# SOIC8-TSSOP8.net
KiCad netlist of a schematic drawn in EAGLE
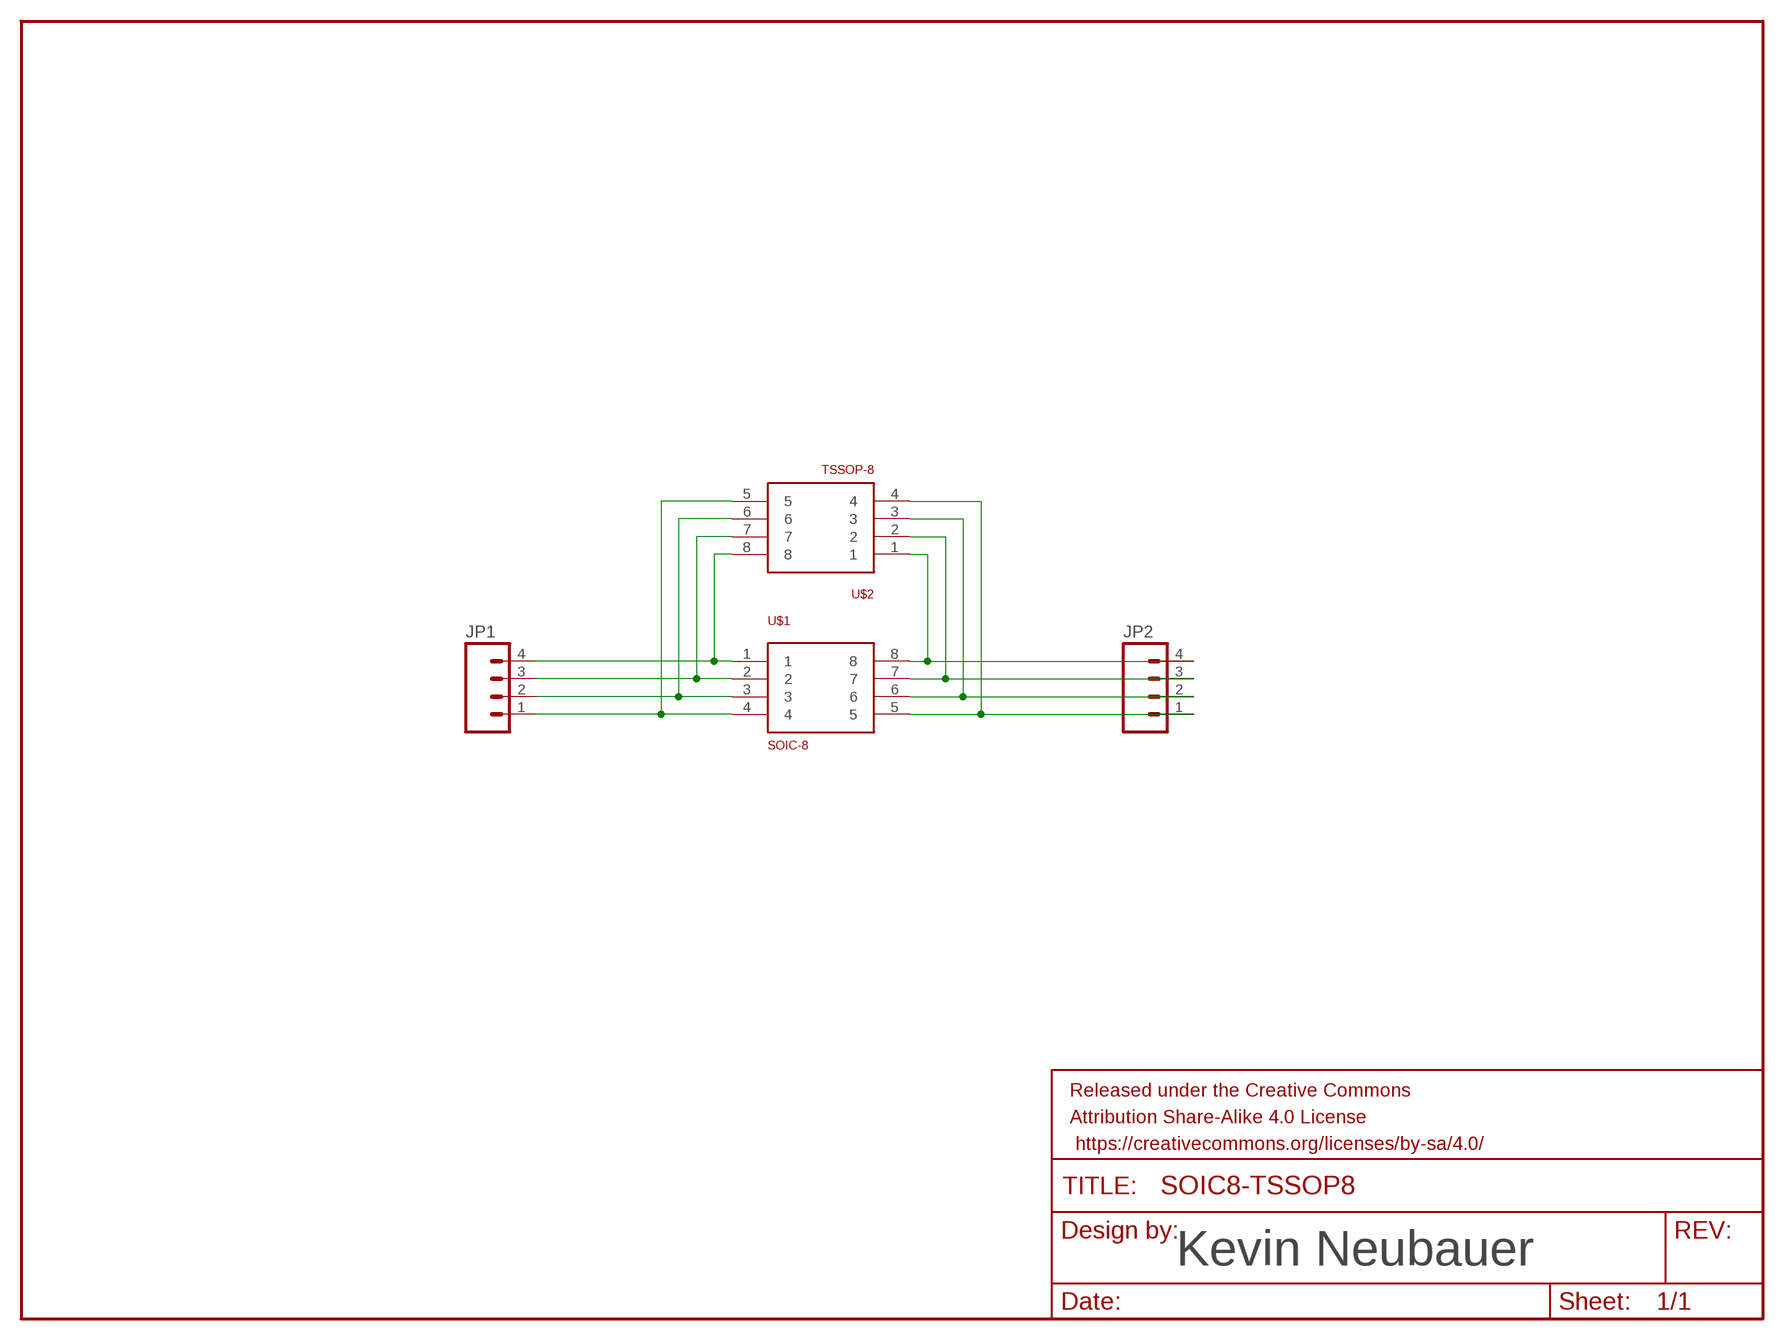
[diagram p0: schematic, sheet 1]

(export (version "E")
  (design (tool "Eeschema 10.0.6"))
  (components
    (comp (ref "FRAME1")
      (value "FRAME-LETTER")
      (footprint "eagle-import:CREATIVE_COMMONS")
      (libsource (lib "eagle-import") (part "FRAME-LETTER"))
    )
    (comp (ref "JP1")
      (value "M04PTH")
      (footprint "eagle-import:1X04")
      (libsource (lib "eagle-import") (part "M04PTH"))
    )
    (comp (ref "JP2")
      (value "M04PTH")
      (footprint "eagle-import:1X04")
      (libsource (lib "eagle-import") (part "M04PTH"))
    )
    (comp (ref "U$1")
      (value "SOIC-8")
      (footprint "eagle-import:SOIC-8")
      (libsource (lib "eagle-import") (part "SOIC-8"))
    )
    (comp (ref "U$2")
      (value "TSSOP-8")
      (footprint "eagle-import:TSSOP8")
      (libsource (lib "eagle-import") (part "TSSOP-8"))
    )
  )
  (nets
    (net (code "1") (name "Net-(JP1-Pad1)") (class "Default")
      (node (ref "JP1") (pin "1") (pinfunction "1_1") (pintype "passive"))
      (node (ref "U$1") (pin "4") (pinfunction "4_4") (pintype "bidirectional"))
      (node (ref "U$2") (pin "5") (pinfunction "5_5") (pintype "bidirectional"))
    )
    (net (code "2") (name "Net-(JP1-Pad2)") (class "Default")
      (node (ref "JP1") (pin "2") (pinfunction "2_2") (pintype "passive"))
      (node (ref "U$1") (pin "3") (pinfunction "3_3") (pintype "bidirectional"))
      (node (ref "U$2") (pin "6") (pinfunction "6_6") (pintype "bidirectional"))
    )
    (net (code "3") (name "Net-(JP1-Pad3)") (class "Default")
      (node (ref "JP1") (pin "3") (pinfunction "3_3") (pintype "passive"))
      (node (ref "U$1") (pin "2") (pinfunction "2_2") (pintype "bidirectional"))
      (node (ref "U$2") (pin "7") (pinfunction "7_7") (pintype "bidirectional"))
    )
    (net (code "4") (name "Net-(JP1-Pad4)") (class "Default")
      (node (ref "JP1") (pin "4") (pinfunction "4_4") (pintype "passive"))
      (node (ref "U$1") (pin "1") (pinfunction "1_1") (pintype "bidirectional"))
      (node (ref "U$2") (pin "8") (pinfunction "8_8") (pintype "bidirectional"))
    )
    (net (code "5") (name "Net-(JP2-Pad1)") (class "Default")
      (node (ref "JP2") (pin "1") (pinfunction "1_1") (pintype "passive"))
      (node (ref "U$1") (pin "5") (pinfunction "5_5") (pintype "bidirectional"))
      (node (ref "U$2") (pin "4") (pinfunction "4_4") (pintype "bidirectional"))
    )
    (net (code "6") (name "Net-(JP2-Pad2)") (class "Default")
      (node (ref "JP2") (pin "2") (pinfunction "2_2") (pintype "passive"))
      (node (ref "U$1") (pin "6") (pinfunction "6_6") (pintype "bidirectional"))
      (node (ref "U$2") (pin "3") (pinfunction "3_3") (pintype "bidirectional"))
    )
    (net (code "7") (name "Net-(JP2-Pad3)") (class "Default")
      (node (ref "JP2") (pin "3") (pinfunction "3_3") (pintype "passive"))
      (node (ref "U$1") (pin "7") (pinfunction "7_7") (pintype "bidirectional"))
      (node (ref "U$2") (pin "2") (pinfunction "2_2") (pintype "bidirectional"))
    )
    (net (code "8") (name "Net-(JP2-Pad4)") (class "Default")
      (node (ref "JP2") (pin "4") (pinfunction "4_4") (pintype "passive"))
      (node (ref "U$1") (pin "8") (pinfunction "8_8") (pintype "bidirectional"))
      (node (ref "U$2") (pin "1") (pinfunction "1_1") (pintype "bidirectional"))
    )
  )
)
